# 25_SATA-SATA_PM0.net
KiCad netlist of a schematic drawn in Altium Designer
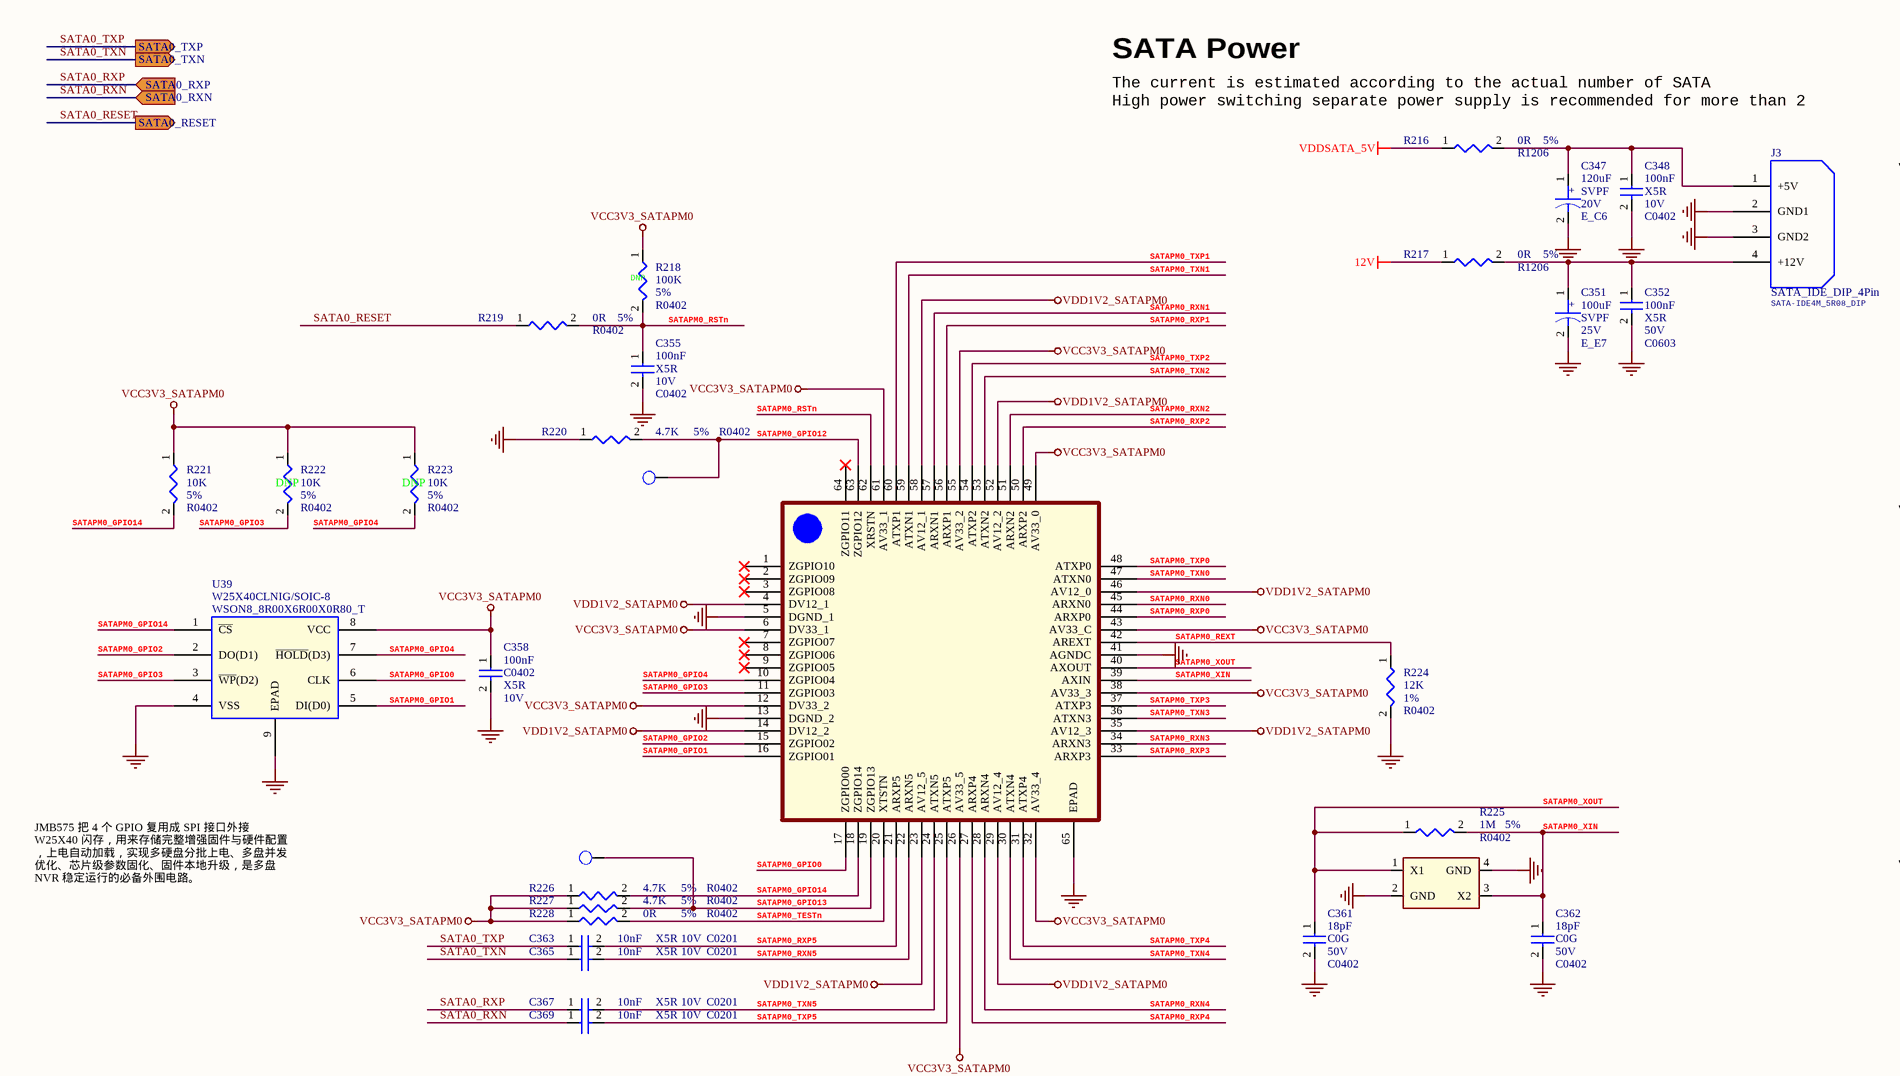
[diagram p0: 25_SATA-SATA PM0.SchDoc, top left]
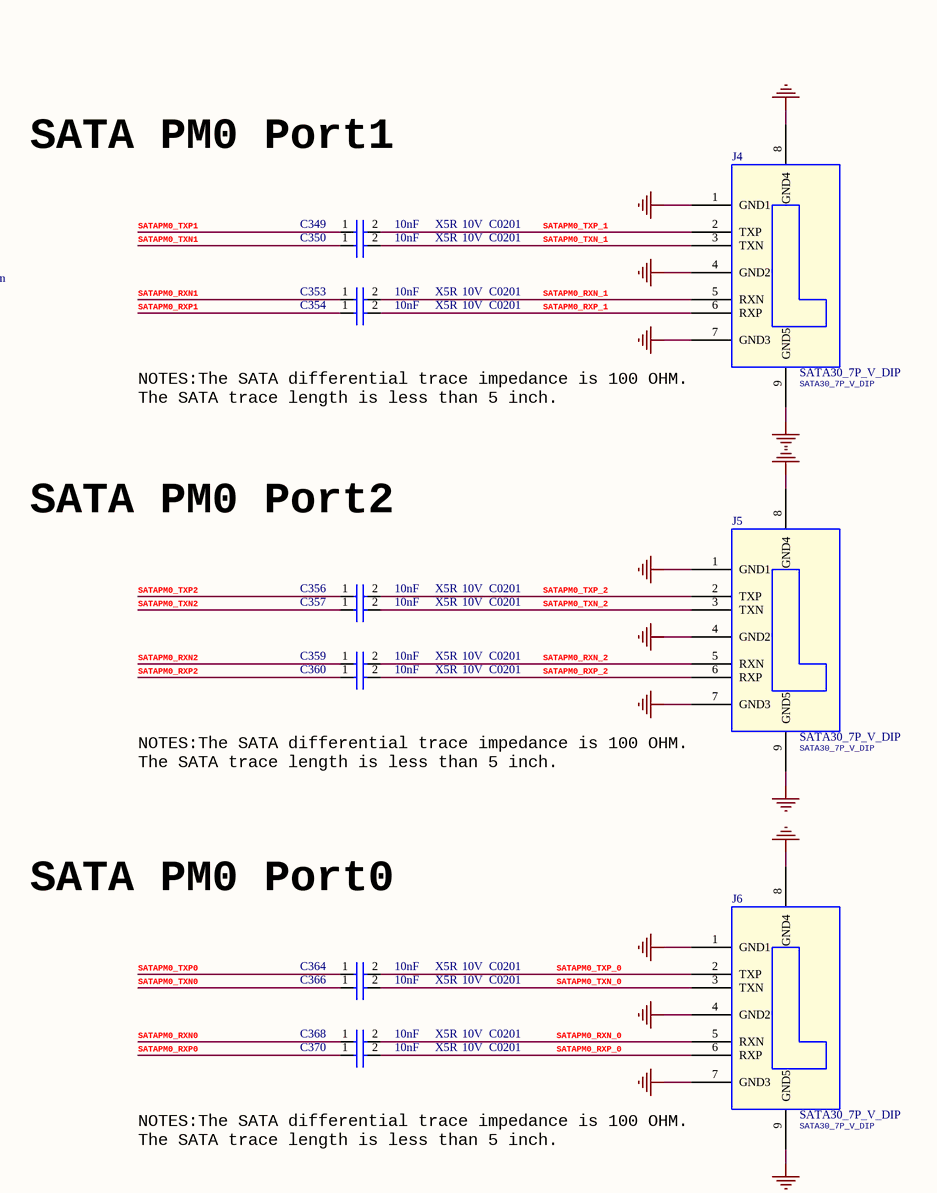
[diagram p1: 25_SATA-SATA PM0.SchDoc, top right]
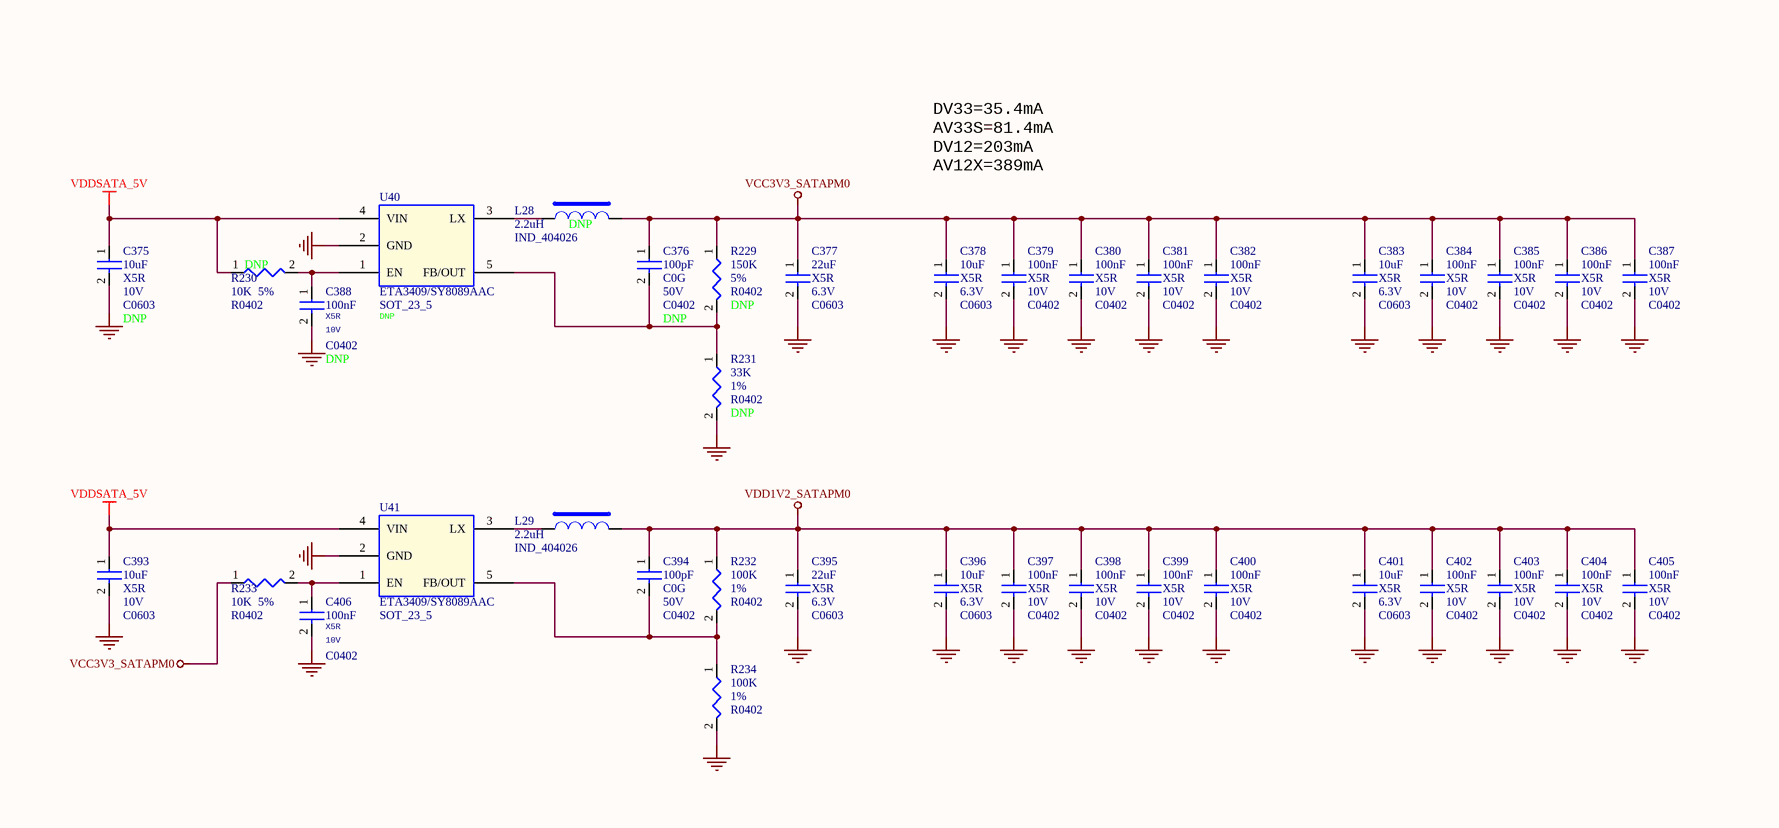
[diagram p2: 25_SATA-SATA PM0.SchDoc, bottom left]
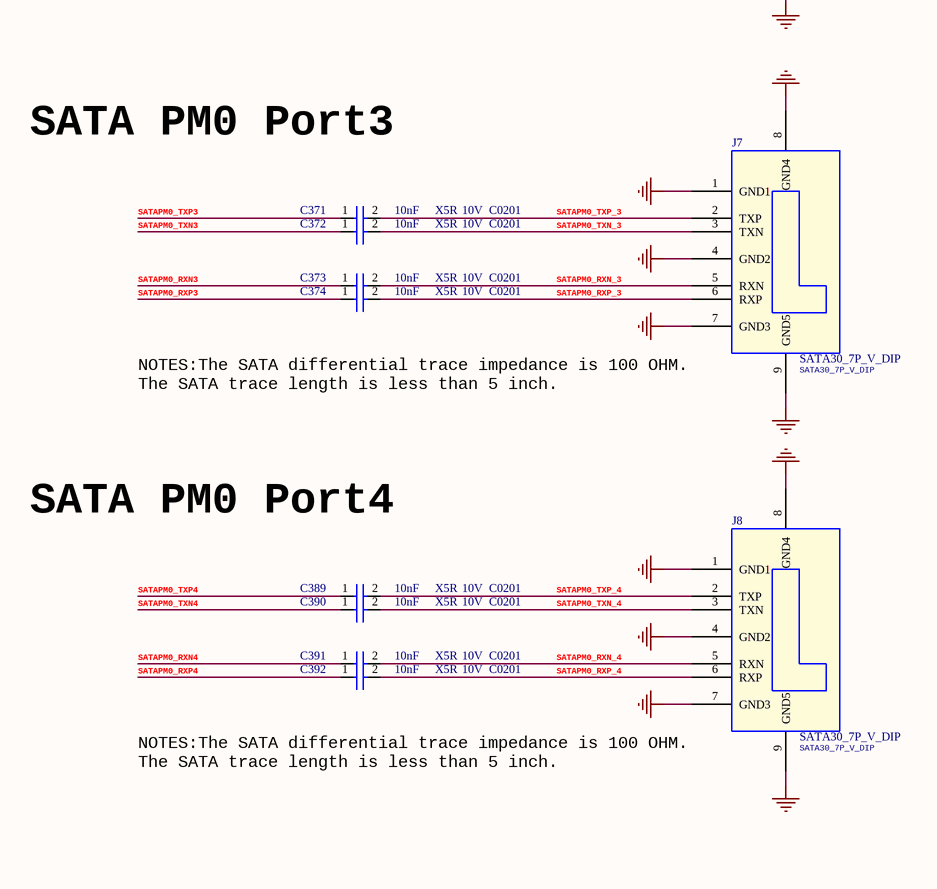
[diagram p3: 25_SATA-SATA PM0.SchDoc, bottom right]

(export (version "E")
  (design (tool "Eeschema 10.0.6"))
  (components
    (comp (ref "C347")
      (value "120uF")
      (footprint "E_C6")
      (description "120uF,20V,25mR,SVPF")
      (fields
        (field (name "VOLTAGE") "20V")
        (field (name "DIELECTRIC") "SVPF")
        (field (name "PCB FOOTPRINT") "E_C6")
        (field (name "MANUFACTURER") "Panasonic")
        (field (name "TOLERANCE") "20%")
        (field (name "CREATED BY") "JJJ")
      )
      (libsource (lib "*") (part "CAP"))
    )
    (comp (ref "C348")
      (value "100nF")
      (footprint "C0402")
      (description "cap,100.00nF,+/-10%,10V,X5R,C0402")
      (fields
        (field (name "VOLTAGE") "10V")
        (field (name "PCB FOOTPRINT") "C0402")
        (field (name "DIELECTRIC") "X5R")
        (field (name "TOLERANCE") "10%")
        (field (name "MANUFACTURER") "TDK")
        (field (name "CREATED BY") "JJJ")
      )
      (libsource (lib "*") (part "CAP NP"))
    )
    (comp (ref "C349")
      (value "10nF")
      (footprint "C0201")
      (description "cap,10.00nF,+/-10%,10V,X5R,C0201")
      (fields
        (field (name "VOLTAGE") "10V")
        (field (name "PCB FOOTPRINT") "C0201")
        (field (name "DIELECTRIC") "X5R")
        (field (name "MANUFACTURER") "TDK")
        (field (name "TOLERANCE") "10%")
        (field (name "CREATED BY") "JJJ")
      )
      (libsource (lib "*") (part "CAP NP"))
    )
    (comp (ref "C350")
      (value "10nF")
      (footprint "C0201")
      (description "cap,10.00nF,+/-10%,10V,X5R,C0201")
      (fields
        (field (name "VOLTAGE") "10V")
        (field (name "PCB FOOTPRINT") "C0201")
        (field (name "DIELECTRIC") "X5R")
        (field (name "MANUFACTURER") "TDK")
        (field (name "TOLERANCE") "10%")
        (field (name "CREATED BY") "JJJ")
      )
      (libsource (lib "*") (part "CAP NP"))
    )
    (comp (ref "C351")
      (value "100uF")
      (footprint "E_E7")
      (description "100uF,25V,24mR,SVPF")
      (fields
        (field (name "VOLTAGE") "25V")
        (field (name "DIELECTRIC") "SVPF")
        (field (name "PCB FOOTPRINT") "E_E7")
        (field (name "MANUFACTURER") "Panasonic")
        (field (name "TOLERANCE") "20%")
        (field (name "CREATED BY") "JJJ")
      )
      (libsource (lib "*") (part "CAP"))
    )
    (comp (ref "C352")
      (value "100nF")
      (footprint "C0603")
      (description "cap,100.00nF,+/-10%,50V,X5R,C0603")
      (fields
        (field (name "VOLTAGE") "50V")
        (field (name "PCB FOOTPRINT") "C0603")
        (field (name "DIELECTRIC") "X5R")
        (field (name "MANUFACTURER") "TDK")
        (field (name "TOLERANCE") "10%")
        (field (name "CREATED BY") "JJJ")
      )
      (libsource (lib "*") (part "CAP NP"))
    )
    (comp (ref "C353")
      (value "10nF")
      (footprint "C0201")
      (description "cap,10.00nF,+/-10%,10V,X5R,C0201")
      (fields
        (field (name "VOLTAGE") "10V")
        (field (name "PCB FOOTPRINT") "C0201")
        (field (name "DIELECTRIC") "X5R")
        (field (name "MANUFACTURER") "TDK")
        (field (name "TOLERANCE") "10%")
        (field (name "CREATED BY") "JJJ")
      )
      (libsource (lib "*") (part "CAP NP"))
    )
    (comp (ref "C354")
      (value "10nF")
      (footprint "C0201")
      (description "cap,10.00nF,+/-10%,10V,X5R,C0201")
      (fields
        (field (name "VOLTAGE") "10V")
        (field (name "PCB FOOTPRINT") "C0201")
        (field (name "DIELECTRIC") "X5R")
        (field (name "MANUFACTURER") "TDK")
        (field (name "TOLERANCE") "10%")
        (field (name "CREATED BY") "JJJ")
      )
      (libsource (lib "*") (part "CAP NP"))
    )
    (comp (ref "C355")
      (value "100nF")
      (footprint "C0402")
      (description "cap,100.00nF,+/-10%,10V,X5R,C0402")
      (fields
        (field (name "VOLTAGE") "10V")
        (field (name "PCB FOOTPRINT") "C0402")
        (field (name "DIELECTRIC") "X5R")
        (field (name "TOLERANCE") "10%")
        (field (name "MANUFACTURER") "TDK")
        (field (name "CREATED BY") "JJJ")
      )
      (libsource (lib "*") (part "CAP NP"))
    )
    (comp (ref "C356")
      (value "10nF")
      (footprint "C0201")
      (description "cap,10.00nF,+/-10%,10V,X5R,C0201")
      (fields
        (field (name "VOLTAGE") "10V")
        (field (name "PCB FOOTPRINT") "C0201")
        (field (name "DIELECTRIC") "X5R")
        (field (name "MANUFACTURER") "TDK")
        (field (name "TOLERANCE") "10%")
        (field (name "CREATED BY") "JJJ")
      )
      (libsource (lib "*") (part "CAP NP"))
    )
    (comp (ref "C357")
      (value "10nF")
      (footprint "C0201")
      (description "cap,10.00nF,+/-10%,10V,X5R,C0201")
      (fields
        (field (name "VOLTAGE") "10V")
        (field (name "PCB FOOTPRINT") "C0201")
        (field (name "DIELECTRIC") "X5R")
        (field (name "MANUFACTURER") "TDK")
        (field (name "TOLERANCE") "10%")
        (field (name "CREATED BY") "JJJ")
      )
      (libsource (lib "*") (part "CAP NP"))
    )
    (comp (ref "C358")
      (value "100nF")
      (footprint "C0402")
      (description "cap,100.00nF,+/-10%,10V,X5R,C0402")
      (fields
        (field (name "VOLTAGE") "10V")
        (field (name "PCB FOOTPRINT") "C0402")
        (field (name "DIELECTRIC") "X5R")
        (field (name "TOLERANCE") "10%")
        (field (name "MANUFACTURER") "TDK")
        (field (name "CREATED BY") "JJJ")
      )
      (libsource (lib "*") (part "CAP NP"))
    )
    (comp (ref "C359")
      (value "10nF")
      (footprint "C0201")
      (description "cap,10.00nF,+/-10%,10V,X5R,C0201")
      (fields
        (field (name "VOLTAGE") "10V")
        (field (name "PCB FOOTPRINT") "C0201")
        (field (name "DIELECTRIC") "X5R")
        (field (name "MANUFACTURER") "TDK")
        (field (name "TOLERANCE") "10%")
        (field (name "CREATED BY") "JJJ")
      )
      (libsource (lib "*") (part "CAP NP"))
    )
    (comp (ref "C360")
      (value "10nF")
      (footprint "C0201")
      (description "cap,10.00nF,+/-10%,10V,X5R,C0201")
      (fields
        (field (name "VOLTAGE") "10V")
        (field (name "PCB FOOTPRINT") "C0201")
        (field (name "DIELECTRIC") "X5R")
        (field (name "MANUFACTURER") "TDK")
        (field (name "TOLERANCE") "10%")
        (field (name "CREATED BY") "JJJ")
      )
      (libsource (lib "*") (part "CAP NP"))
    )
    (comp (ref "C361")
      (value "18pF")
      (footprint "C0402")
      (description "cap,18.00pF,+/-5%,50V,C0G,C0402")
      (fields
        (field (name "VOLTAGE") "50V")
        (field (name "PCB FOOTPRINT") "C0402")
        (field (name "DIELECTRIC") "C0G")
        (field (name "TOLERANCE") "5%")
        (field (name "MANUFACTURER") "TDK")
        (field (name "CREATED BY") "JJJ")
      )
      (libsource (lib "*") (part "CAP NP"))
    )
    (comp (ref "C362")
      (value "18pF")
      (footprint "C0402")
      (description "cap,18.00pF,+/-5%,50V,C0G,C0402")
      (fields
        (field (name "VOLTAGE") "50V")
        (field (name "PCB FOOTPRINT") "C0402")
        (field (name "DIELECTRIC") "C0G")
        (field (name "TOLERANCE") "5%")
        (field (name "MANUFACTURER") "TDK")
        (field (name "CREATED BY") "JJJ")
      )
      (libsource (lib "*") (part "CAP NP"))
    )
    (comp (ref "C363")
      (value "10nF")
      (footprint "C0201")
      (description "cap,10.00nF,+/-10%,10V,X5R,C0201")
      (fields
        (field (name "VOLTAGE") "10V")
        (field (name "PCB FOOTPRINT") "C0201")
        (field (name "DIELECTRIC") "X5R")
        (field (name "TOLERANCE") "10%")
        (field (name "MANUFACTURER") "TDK")
        (field (name "CREATED BY") "JJJ")
      )
      (libsource (lib "*") (part "CAP NP"))
    )
    (comp (ref "C364")
      (value "10nF")
      (footprint "C0201")
      (description "cap,10.00nF,+/-10%,10V,X5R,C0201")
      (fields
        (field (name "VOLTAGE") "10V")
        (field (name "PCB FOOTPRINT") "C0201")
        (field (name "DIELECTRIC") "X5R")
        (field (name "MANUFACTURER") "TDK")
        (field (name "TOLERANCE") "10%")
        (field (name "CREATED BY") "JJJ")
      )
      (libsource (lib "*") (part "CAP NP"))
    )
    (comp (ref "C365")
      (value "10nF")
      (footprint "C0201")
      (description "cap,10.00nF,+/-10%,10V,X5R,C0201")
      (fields
        (field (name "VOLTAGE") "10V")
        (field (name "PCB FOOTPRINT") "C0201")
        (field (name "DIELECTRIC") "X5R")
        (field (name "TOLERANCE") "10%")
        (field (name "MANUFACTURER") "TDK")
        (field (name "CREATED BY") "JJJ")
      )
      (libsource (lib "*") (part "CAP NP"))
    )
    (comp (ref "C366")
      (value "10nF")
      (footprint "C0201")
      (description "cap,10.00nF,+/-10%,10V,X5R,C0201")
      (fields
        (field (name "VOLTAGE") "10V")
        (field (name "PCB FOOTPRINT") "C0201")
        (field (name "DIELECTRIC") "X5R")
        (field (name "MANUFACTURER") "TDK")
        (field (name "TOLERANCE") "10%")
        (field (name "CREATED BY") "JJJ")
      )
      (libsource (lib "*") (part "CAP NP"))
    )
    (comp (ref "C367")
      (value "10nF")
      (footprint "C0201")
      (description "cap,10.00nF,+/-10%,10V,X5R,C0201")
      (fields
        (field (name "VOLTAGE") "10V")
        (field (name "PCB FOOTPRINT") "C0201")
        (field (name "DIELECTRIC") "X5R")
        (field (name "TOLERANCE") "10%")
        (field (name "MANUFACTURER") "TDK")
        (field (name "CREATED BY") "JJJ")
      )
      (libsource (lib "*") (part "CAP NP"))
    )
    (comp (ref "C368")
      (value "10nF")
      (footprint "C0201")
      (description "cap,10.00nF,+/-10%,10V,X5R,C0201")
      (fields
        (field (name "VOLTAGE") "10V")
        (field (name "PCB FOOTPRINT") "C0201")
        (field (name "DIELECTRIC") "X5R")
        (field (name "MANUFACTURER") "TDK")
        (field (name "TOLERANCE") "10%")
        (field (name "CREATED BY") "JJJ")
      )
      (libsource (lib "*") (part "CAP NP"))
    )
    (comp (ref "C369")
      (value "10nF")
      (footprint "C0201")
      (description "cap,10.00nF,+/-10%,10V,X5R,C0201")
      (fields
        (field (name "VOLTAGE") "10V")
        (field (name "PCB FOOTPRINT") "C0201")
        (field (name "DIELECTRIC") "X5R")
        (field (name "TOLERANCE") "10%")
        (field (name "MANUFACTURER") "TDK")
        (field (name "CREATED BY") "JJJ")
      )
      (libsource (lib "*") (part "CAP NP"))
    )
    (comp (ref "C370")
      (value "10nF")
      (footprint "C0201")
      (description "cap,10.00nF,+/-10%,10V,X5R,C0201")
      (fields
        (field (name "VOLTAGE") "10V")
        (field (name "PCB FOOTPRINT") "C0201")
        (field (name "DIELECTRIC") "X5R")
        (field (name "MANUFACTURER") "TDK")
        (field (name "TOLERANCE") "10%")
        (field (name "CREATED BY") "JJJ")
      )
      (libsource (lib "*") (part "CAP NP"))
    )
    (comp (ref "C371")
      (value "10nF")
      (footprint "C0201")
      (description "cap,10.00nF,+/-10%,10V,X5R,C0201")
      (fields
        (field (name "VOLTAGE") "10V")
        (field (name "PCB FOOTPRINT") "C0201")
        (field (name "DIELECTRIC") "X5R")
        (field (name "MANUFACTURER") "TDK")
        (field (name "TOLERANCE") "10%")
        (field (name "CREATED BY") "JJJ")
      )
      (libsource (lib "*") (part "CAP NP"))
    )
    (comp (ref "C372")
      (value "10nF")
      (footprint "C0201")
      (description "cap,10.00nF,+/-10%,10V,X5R,C0201")
      (fields
        (field (name "VOLTAGE") "10V")
        (field (name "PCB FOOTPRINT") "C0201")
        (field (name "DIELECTRIC") "X5R")
        (field (name "MANUFACTURER") "TDK")
        (field (name "TOLERANCE") "10%")
        (field (name "CREATED BY") "JJJ")
      )
      (libsource (lib "*") (part "CAP NP"))
    )
    (comp (ref "C373")
      (value "10nF")
      (footprint "C0201")
      (description "cap,10.00nF,+/-10%,10V,X5R,C0201")
      (fields
        (field (name "VOLTAGE") "10V")
        (field (name "PCB FOOTPRINT") "C0201")
        (field (name "DIELECTRIC") "X5R")
        (field (name "MANUFACTURER") "TDK")
        (field (name "TOLERANCE") "10%")
        (field (name "CREATED BY") "JJJ")
      )
      (libsource (lib "*") (part "CAP NP"))
    )
    (comp (ref "C374")
      (value "10nF")
      (footprint "C0201")
      (description "cap,10.00nF,+/-10%,10V,X5R,C0201")
      (fields
        (field (name "VOLTAGE") "10V")
        (field (name "PCB FOOTPRINT") "C0201")
        (field (name "DIELECTRIC") "X5R")
        (field (name "MANUFACTURER") "TDK")
        (field (name "TOLERANCE") "10%")
        (field (name "CREATED BY") "JJJ")
      )
      (libsource (lib "*") (part "CAP NP"))
    )
    (comp (ref "C375")
      (value "10uF")
      (footprint "C0603")
      (description "cap,10.00uF,+/-10%,10V,X5R,C0603")
      (fields
        (field (name "VOLTAGE") "10V")
        (field (name "PCB FOOTPRINT") "C0603")
        (field (name "DIELECTRIC") "X5R")
        (field (name "MANUFACTURER") "TDK")
        (field (name "TOLERANCE") "10%")
        (field (name "OPTION") "DNP")
        (field (name "CREATED BY") "JJJ")
      )
      (libsource (lib "*") (part "CAP NP"))
    )
    (comp (ref "C376")
      (value "100pF")
      (footprint "C0402")
      (description "cap,100.00pF,+/-10%,50V,C0G,C0402")
      (fields
        (field (name "VOLTAGE") "50V")
        (field (name "PCB FOOTPRINT") "C0402")
        (field (name "DIELECTRIC") "C0G")
        (field (name "TOLERANCE") "10%")
        (field (name "MANUFACTURER") "TDK")
        (field (name "OPTION") "DNP")
        (field (name "CREATED BY") "JJJ")
      )
      (libsource (lib "*") (part "CAP NP"))
    )
    (comp (ref "C377")
      (value "22uF")
      (footprint "C0603")
      (description "cap,22.00uF,+/-20%,6.3V,X5R,C0603")
      (fields
        (field (name "VOLTAGE") "6.3V")
        (field (name "PCB FOOTPRINT") "C0603")
        (field (name "DIELECTRIC") "X5R")
        (field (name "MANUFACTURER") "TDK")
        (field (name "TOLERANCE") "20%")
        (field (name "CREATED BY") "JJJ")
      )
      (libsource (lib "*") (part "CAP NP"))
    )
    (comp (ref "C378")
      (value "10uF")
      (footprint "C0603")
      (description "cap,10.00uF,+/-10%,6.3V,X5R,C0603")
      (fields
        (field (name "VOLTAGE") "6.3V")
        (field (name "PCB FOOTPRINT") "C0603")
        (field (name "DIELECTRIC") "X5R")
        (field (name "TOLERANCE") "10%")
        (field (name "MANUFACTURER") "TDK")
        (field (name "CREATED BY") "JJJ")
      )
      (libsource (lib "*") (part "CAP NP"))
    )
    (comp (ref "C379")
      (value "100nF")
      (footprint "C0402")
      (description "cap,100.00nF,+/-10%,10V,X5R,C0402")
      (fields
        (field (name "VOLTAGE") "10V")
        (field (name "PCB FOOTPRINT") "C0402")
        (field (name "DIELECTRIC") "X5R")
        (field (name "MANUFACTURER") "TDK")
        (field (name "TOLERANCE") "10%")
        (field (name "CREATED BY") "JJJ")
      )
      (libsource (lib "*") (part "CAP NP"))
    )
    (comp (ref "C380")
      (value "100nF")
      (footprint "C0402")
      (description "cap,100.00nF,+/-10%,10V,X5R,C0402")
      (fields
        (field (name "VOLTAGE") "10V")
        (field (name "PCB FOOTPRINT") "C0402")
        (field (name "DIELECTRIC") "X5R")
        (field (name "MANUFACTURER") "TDK")
        (field (name "TOLERANCE") "10%")
        (field (name "CREATED BY") "JJJ")
      )
      (libsource (lib "*") (part "CAP NP"))
    )
    (comp (ref "C381")
      (value "100nF")
      (footprint "C0402")
      (description "cap,100.00nF,+/-10%,10V,X5R,C0402")
      (fields
        (field (name "VOLTAGE") "10V")
        (field (name "PCB FOOTPRINT") "C0402")
        (field (name "DIELECTRIC") "X5R")
        (field (name "MANUFACTURER") "TDK")
        (field (name "TOLERANCE") "10%")
        (field (name "CREATED BY") "JJJ")
      )
      (libsource (lib "*") (part "CAP NP"))
    )
    (comp (ref "C382")
      (value "100nF")
      (footprint "C0402")
      (description "cap,100.00nF,+/-10%,10V,X5R,C0402")
      (fields
        (field (name "VOLTAGE") "10V")
        (field (name "PCB FOOTPRINT") "C0402")
        (field (name "DIELECTRIC") "X5R")
        (field (name "MANUFACTURER") "TDK")
        (field (name "TOLERANCE") "10%")
        (field (name "CREATED BY") "JJJ")
      )
      (libsource (lib "*") (part "CAP NP"))
    )
    (comp (ref "C383")
      (value "10uF")
      (footprint "C0603")
      (description "cap,10.00uF,+/-10%,6.3V,X5R,C0603")
      (fields
        (field (name "VOLTAGE") "6.3V")
        (field (name "PCB FOOTPRINT") "C0603")
        (field (name "DIELECTRIC") "X5R")
        (field (name "TOLERANCE") "10%")
        (field (name "MANUFACTURER") "TDK")
        (field (name "CREATED BY") "JJJ")
      )
      (libsource (lib "*") (part "CAP NP"))
    )
    (comp (ref "C384")
      (value "100nF")
      (footprint "C0402")
      (description "cap,100.00nF,+/-10%,10V,X5R,C0402")
      (fields
        (field (name "VOLTAGE") "10V")
        (field (name "PCB FOOTPRINT") "C0402")
        (field (name "DIELECTRIC") "X5R")
        (field (name "MANUFACTURER") "TDK")
        (field (name "TOLERANCE") "10%")
        (field (name "CREATED BY") "JJJ")
      )
      (libsource (lib "*") (part "CAP NP"))
    )
    (comp (ref "C385")
      (value "100nF")
      (footprint "C0402")
      (description "cap,100.00nF,+/-10%,10V,X5R,C0402")
      (fields
        (field (name "VOLTAGE") "10V")
        (field (name "PCB FOOTPRINT") "C0402")
        (field (name "DIELECTRIC") "X5R")
        (field (name "MANUFACTURER") "TDK")
        (field (name "TOLERANCE") "10%")
        (field (name "CREATED BY") "JJJ")
      )
      (libsource (lib "*") (part "CAP NP"))
    )
    (comp (ref "C386")
      (value "100nF")
      (footprint "C0402")
      (description "cap,100.00nF,+/-10%,10V,X5R,C0402")
      (fields
        (field (name "VOLTAGE") "10V")
        (field (name "PCB FOOTPRINT") "C0402")
        (field (name "DIELECTRIC") "X5R")
        (field (name "MANUFACTURER") "TDK")
        (field (name "TOLERANCE") "10%")
        (field (name "CREATED BY") "JJJ")
      )
      (libsource (lib "*") (part "CAP NP"))
    )
    (comp (ref "C387")
      (value "100nF")
      (footprint "C0402")
      (description "cap,100.00nF,+/-10%,10V,X5R,C0402")
      (fields
        (field (name "VOLTAGE") "10V")
        (field (name "PCB FOOTPRINT") "C0402")
        (field (name "DIELECTRIC") "X5R")
        (field (name "MANUFACTURER") "TDK")
        (field (name "TOLERANCE") "10%")
        (field (name "CREATED BY") "JJJ")
      )
      (libsource (lib "*") (part "CAP NP"))
    )
    (comp (ref "C388")
      (value "100nF")
      (footprint "C0402")
      (description "cap,100.00nF,+/-10%,10V,X5R,C0402")
      (fields
        (field (name "VOLTAGE") "10V")
        (field (name "PCB FOOTPRINT") "C0402")
        (field (name "DIELECTRIC") "X5R")
        (field (name "TOLERANCE") "10%")
        (field (name "MANUFACTURER") "TDK")
        (field (name "OPTION") "DNP")
        (field (name "CREATED BY") "JJJ")
      )
      (libsource (lib "*") (part "CAP NP"))
    )
    (comp (ref "C389")
      (value "10nF")
      (footprint "C0201")
      (description "cap,10.00nF,+/-10%,10V,X5R,C0201")
      (fields
        (field (name "VOLTAGE") "10V")
        (field (name "PCB FOOTPRINT") "C0201")
        (field (name "DIELECTRIC") "X5R")
        (field (name "MANUFACTURER") "TDK")
        (field (name "TOLERANCE") "10%")
        (field (name "CREATED BY") "JJJ")
      )
      (libsource (lib "*") (part "CAP NP"))
    )
    (comp (ref "C390")
      (value "10nF")
      (footprint "C0201")
      (description "cap,10.00nF,+/-10%,10V,X5R,C0201")
      (fields
        (field (name "VOLTAGE") "10V")
        (field (name "PCB FOOTPRINT") "C0201")
        (field (name "DIELECTRIC") "X5R")
        (field (name "MANUFACTURER") "TDK")
        (field (name "TOLERANCE") "10%")
        (field (name "CREATED BY") "JJJ")
      )
      (libsource (lib "*") (part "CAP NP"))
    )
    (comp (ref "C391")
      (value "10nF")
      (footprint "C0201")
      (description "cap,10.00nF,+/-10%,10V,X5R,C0201")
      (fields
        (field (name "VOLTAGE") "10V")
        (field (name "PCB FOOTPRINT") "C0201")
        (field (name "DIELECTRIC") "X5R")
        (field (name "MANUFACTURER") "TDK")
        (field (name "TOLERANCE") "10%")
        (field (name "CREATED BY") "JJJ")
      )
      (libsource (lib "*") (part "CAP NP"))
    )
    (comp (ref "C392")
      (value "10nF")
      (footprint "C0201")
      (description "cap,10.00nF,+/-10%,10V,X5R,C0201")
      (fields
        (field (name "VOLTAGE") "10V")
        (field (name "PCB FOOTPRINT") "C0201")
        (field (name "DIELECTRIC") "X5R")
        (field (name "MANUFACTURER") "TDK")
        (field (name "TOLERANCE") "10%")
        (field (name "CREATED BY") "JJJ")
      )
      (libsource (lib "*") (part "CAP NP"))
    )
    (comp (ref "C393")
      (value "10uF")
      (footprint "C0603")
      (description "cap,10.00uF,+/-10%,10V,X5R,C0603")
      (fields
        (field (name "VOLTAGE") "10V")
        (field (name "PCB FOOTPRINT") "C0603")
        (field (name "DIELECTRIC") "X5R")
        (field (name "TOLERANCE") "10%")
        (field (name "MANUFACTURER") "TDK")
        (field (name "CREATED BY") "JJJ")
      )
      (libsource (lib "*") (part "CAP NP"))
    )
    (comp (ref "C394")
      (value "100pF")
      (footprint "C0402")
      (description "cap,100.00pF,+/-10%,50V,C0G,C0402")
      (fields
        (field (name "VOLTAGE") "50V")
        (field (name "PCB FOOTPRINT") "C0402")
        (field (name "DIELECTRIC") "C0G")
        (field (name "MANUFACTURER") "TDK")
        (field (name "TOLERANCE") "10%")
        (field (name "CREATED BY") "JJJ")
      )
      (libsource (lib "*") (part "CAP NP"))
    )
    (comp (ref "C395")
      (value "22uF")
      (footprint "C0603")
      (description "cap,22.00uF,+/-20%,6.3V,X5R,C0603")
      (fields
        (field (name "VOLTAGE") "6.3V")
        (field (name "PCB FOOTPRINT") "C0603")
        (field (name "DIELECTRIC") "X5R")
        (field (name "TOLERANCE") "20%")
        (field (name "MANUFACTURER") "TDK")
        (field (name "CREATED BY") "JJJ")
      )
      (libsource (lib "*") (part "CAP NP"))
    )
    (comp (ref "C396")
      (value "10uF")
      (footprint "C0603")
      (description "cap,10.00uF,+/-10%,6.3V,X5R,C0603")
      (fields
        (field (name "VOLTAGE") "6.3V")
        (field (name "PCB FOOTPRINT") "C0603")
        (field (name "DIELECTRIC") "X5R")
        (field (name "TOLERANCE") "10%")
        (field (name "MANUFACTURER") "TDK")
        (field (name "CREATED BY") "JJJ")
      )
      (libsource (lib "*") (part "CAP NP"))
    )
    (comp (ref "C397")
      (value "100nF")
      (footprint "C0402")
      (description "cap,100.00nF,+/-10%,10V,X5R,C0402")
      (fields
        (field (name "VOLTAGE") "10V")
        (field (name "PCB FOOTPRINT") "C0402")
        (field (name "DIELECTRIC") "X5R")
        (field (name "MANUFACTURER") "TDK")
        (field (name "TOLERANCE") "10%")
        (field (name "CREATED BY") "JJJ")
      )
      (libsource (lib "*") (part "CAP NP"))
    )
    (comp (ref "C398")
      (value "100nF")
      (footprint "C0402")
      (description "cap,100.00nF,+/-10%,10V,X5R,C0402")
      (fields
        (field (name "VOLTAGE") "10V")
        (field (name "PCB FOOTPRINT") "C0402")
        (field (name "DIELECTRIC") "X5R")
        (field (name "MANUFACTURER") "TDK")
        (field (name "TOLERANCE") "10%")
        (field (name "CREATED BY") "JJJ")
      )
      (libsource (lib "*") (part "CAP NP"))
    )
    (comp (ref "C399")
      (value "100nF")
      (footprint "C0402")
      (description "cap,100.00nF,+/-10%,10V,X5R,C0402")
      (fields
        (field (name "VOLTAGE") "10V")
        (field (name "PCB FOOTPRINT") "C0402")
        (field (name "DIELECTRIC") "X5R")
        (field (name "MANUFACTURER") "TDK")
        (field (name "TOLERANCE") "10%")
        (field (name "CREATED BY") "JJJ")
      )
      (libsource (lib "*") (part "CAP NP"))
    )
    (comp (ref "C400")
      (value "100nF")
      (footprint "C0402")
      (description "cap,100.00nF,+/-10%,10V,X5R,C0402")
      (fields
        (field (name "VOLTAGE") "10V")
        (field (name "PCB FOOTPRINT") "C0402")
        (field (name "DIELECTRIC") "X5R")
        (field (name "MANUFACTURER") "TDK")
        (field (name "TOLERANCE") "10%")
        (field (name "CREATED BY") "JJJ")
      )
      (libsource (lib "*") (part "CAP NP"))
    )
    (comp (ref "C401")
      (value "10uF")
      (footprint "C0603")
      (description "cap,10.00uF,+/-10%,6.3V,X5R,C0603")
      (fields
        (field (name "VOLTAGE") "6.3V")
        (field (name "PCB FOOTPRINT") "C0603")
        (field (name "DIELECTRIC") "X5R")
        (field (name "TOLERANCE") "10%")
        (field (name "MANUFACTURER") "TDK")
        (field (name "CREATED BY") "JJJ")
      )
      (libsource (lib "*") (part "CAP NP"))
    )
    (comp (ref "C402")
      (value "100nF")
      (footprint "C0402")
      (description "cap,100.00nF,+/-10%,10V,X5R,C0402")
      (fields
        (field (name "VOLTAGE") "10V")
        (field (name "PCB FOOTPRINT") "C0402")
        (field (name "DIELECTRIC") "X5R")
        (field (name "MANUFACTURER") "TDK")
        (field (name "TOLERANCE") "10%")
        (field (name "CREATED BY") "JJJ")
      )
      (libsource (lib "*") (part "CAP NP"))
    )
    (comp (ref "C403")
      (value "100nF")
      (footprint "C0402")
      (description "cap,100.00nF,+/-10%,10V,X5R,C0402")
      (fields
        (field (name "VOLTAGE") "10V")
        (field (name "PCB FOOTPRINT") "C0402")
        (field (name "DIELECTRIC") "X5R")
        (field (name "MANUFACTURER") "TDK")
        (field (name "TOLERANCE") "10%")
        (field (name "CREATED BY") "JJJ")
      )
      (libsource (lib "*") (part "CAP NP"))
    )
    (comp (ref "C404")
      (value "100nF")
      (footprint "C0402")
      (description "cap,100.00nF,+/-10%,10V,X5R,C0402")
      (fields
        (field (name "VOLTAGE") "10V")
        (field (name "PCB FOOTPRINT") "C0402")
        (field (name "DIELECTRIC") "X5R")
        (field (name "MANUFACTURER") "TDK")
        (field (name "TOLERANCE") "10%")
        (field (name "CREATED BY") "JJJ")
      )
      (libsource (lib "*") (part "CAP NP"))
    )
    (comp (ref "C405")
      (value "100nF")
      (footprint "C0402")
      (description "cap,100.00nF,+/-10%,10V,X5R,C0402")
      (fields
        (field (name "VOLTAGE") "10V")
        (field (name "PCB FOOTPRINT") "C0402")
        (field (name "DIELECTRIC") "X5R")
        (field (name "MANUFACTURER") "TDK")
        (field (name "TOLERANCE") "10%")
        (field (name "CREATED BY") "JJJ")
      )
      (libsource (lib "*") (part "CAP NP"))
    )
    (comp (ref "C406")
      (value "100nF")
      (footprint "C0402")
      (description "cap,100.00nF,+/-10%,10V,X5R,C0402")
      (fields
        (field (name "VOLTAGE") "10V")
        (field (name "PCB FOOTPRINT") "C0402")
        (field (name "DIELECTRIC") "X5R")
        (field (name "MANUFACTURER") "TDK")
        (field (name "TOLERANCE") "10%")
        (field (name "CREATED BY") "JJJ")
      )
      (libsource (lib "*") (part "CAP NP"))
    )
    (comp (ref "J3")
      (value "SATA_IDE_DIP_4Pin")
      (footprint "SATA-IDE4M_5R08_DIP")
      (fields (field (name "PCB FOOTPRINT") "SATA-IDE4M_5R08_DIP"))
      (libsource (lib "*") (part "SATA_IDE_DIP_0"))
    )
    (comp (ref "J4")
      (value "SATA30_7P_V_DIP")
      (footprint "SATA30_7P_V_DIP")
      (fields (field (name "PCB FOOTPRINT") "SATA30_7P_V_DIP"))
      (libsource (lib "*") (part "SATA_DIP_0"))
    )
    (comp (ref "J5")
      (value "SATA30_7P_V_DIP")
      (footprint "SATA30_7P_V_DIP")
      (fields (field (name "PCB FOOTPRINT") "SATA30_7P_V_DIP"))
      (libsource (lib "*") (part "SATA_DIP_0"))
    )
    (comp (ref "J6")
      (value "SATA30_7P_V_DIP")
      (footprint "SATA30_7P_V_DIP")
      (fields (field (name "PCB FOOTPRINT") "SATA30_7P_V_DIP"))
      (libsource (lib "*") (part "SATA_DIP_0"))
    )
    (comp (ref "J7")
      (value "SATA30_7P_V_DIP")
      (footprint "SATA30_7P_V_DIP")
      (fields (field (name "PCB FOOTPRINT") "SATA30_7P_V_DIP"))
      (libsource (lib "*") (part "SATA_DIP_0"))
    )
    (comp (ref "J8")
      (value "SATA30_7P_V_DIP")
      (footprint "SATA30_7P_V_DIP")
      (fields (field (name "PCB FOOTPRINT") "SATA30_7P_V_DIP"))
      (libsource (lib "*") (part "SATA_DIP_0"))
    )
    (comp (ref "L28")
      (value "2.2uH")
      (footprint "IND_404026")
      (description "Power Inductor,2.2uH,0.2,IND_404026")
      (fields
        (field (name "PCB FOOTPRINT") "IND_404026")
        (field (name "TOLERANCE") "20%")
        (field (name "MANUFACTURER") "sunlord")
        (field (name "OPTION") "DNP")
        (field (name "CREATED BY") "YTL")
      )
      (libsource (lib "*") (part "INDUCTORS OF FERRITE_Dup1"))
    )
    (comp (ref "L29")
      (value "2.2uH")
      (footprint "IND_404026")
      (description "Power Inductor,2.2uH,0.2,IND_404026")
      (fields
        (field (name "PCB FOOTPRINT") "IND_404026")
        (field (name "MANUFACTURER") "sunlord")
        (field (name "TOLERANCE") "20%")
        (field (name "CREATED BY") "YTL")
      )
      (libsource (lib "*") (part "INDUCTORS OF FERRITE_Dup1"))
    )
    (comp (ref "R216")
      (value "0R")
      (footprint "R0402")
      (description "通用厚膜电阻,0R,+/-5%,R1206,1/4W.")
      (fields
        (field (name "PCB FOOTPRINT") "R1206")
        (field (name "TOLERANCE") "5%")
        (field (name "MANUFACTURER") "YAGEO")
        (field (name "CREATED BY") "YTL")
      )
      (libsource (lib "*") (part "RESISTOR_Dup1"))
    )
    (comp (ref "R217")
      (value "0R")
      (footprint "R0402")
      (description "通用厚膜电阻,0R,+/-5%,R1206,1/4W.")
      (fields
        (field (name "PCB FOOTPRINT") "R1206")
        (field (name "TOLERANCE") "5%")
        (field (name "MANUFACTURER") "YAGEO")
        (field (name "CREATED BY") "YTL")
      )
      (libsource (lib "*") (part "RESISTOR_Dup1"))
    )
    (comp (ref "R218")
      (value "100K")
      (footprint "R0402")
      (description "通用厚膜电阻,100K,+/-5%,R0402,1/16W.")
      (fields
        (field (name "PCB FOOTPRINT") "R0402")
        (field (name "TOLERANCE") "5%")
        (field (name "MANUFACTURER") "YAGEO")
        (field (name "OPTION") "DNP")
        (field (name "CREATED BY") "YTL")
      )
      (libsource (lib "*") (part "RESISTOR_Dup1"))
    )
    (comp (ref "R219")
      (value "0R")
      (footprint "R0402")
      (description "通用厚膜电阻,0R,+/-5%,R0402,1/16W.")
      (fields
        (field (name "PCB FOOTPRINT") "R0402")
        (field (name "TOLERANCE") "5%")
        (field (name "MANUFACTURER") "YAGEO")
        (field (name "CREATED BY") "YTL")
      )
      (libsource (lib "*") (part "RESISTOR_Dup1"))
    )
    (comp (ref "R220")
      (value "4.7K")
      (footprint "R0402")
      (description "通用厚膜电阻,4K7,+/-5%,R0402,1/16W.")
      (fields
        (field (name "PCB FOOTPRINT") "R0402")
        (field (name "TOLERANCE") "5%")
        (field (name "MANUFACTURER") "YAGEO")
        (field (name "CREATED BY") "YTL")
      )
      (libsource (lib "*") (part "RESISTOR_Dup1"))
    )
    (comp (ref "R221")
      (value "10K")
      (footprint "R0402")
      (description "通用厚膜电阻,10K,+/-5%,R0402,1/16W.")
      (fields
        (field (name "PCB FOOTPRINT") "R0402")
        (field (name "TOLERANCE") "5%")
        (field (name "MANUFACTURER") "YAGEO")
        (field (name "CREATED BY") "YTL")
      )
      (libsource (lib "*") (part "RESISTOR_Dup1"))
    )
    (comp (ref "R222")
      (value "10K")
      (footprint "R0402")
      (description "通用厚膜电阻,10K,+/-5%,R0402,1/16W.")
      (fields
        (field (name "PCB FOOTPRINT") "R0402")
        (field (name "TOLERANCE") "5%")
        (field (name "OPTION") "DNP")
        (field (name "MANUFACTURER") "YAGEO")
        (field (name "CREATED BY") "YTL")
      )
      (libsource (lib "*") (part "RESISTOR_Dup1"))
    )
    (comp (ref "R223")
      (value "10K")
      (footprint "R0402")
      (description "通用厚膜电阻,10K,+/-5%,R0402,1/16W.")
      (fields
        (field (name "PCB FOOTPRINT") "R0402")
        (field (name "TOLERANCE") "5%")
        (field (name "MANUFACTURER") "YAGEO")
        (field (name "OPTION") "DNP")
        (field (name "CREATED BY") "YTL")
      )
      (libsource (lib "*") (part "RESISTOR_Dup1"))
    )
    (comp (ref "R224")
      (value "12K")
      (footprint "R0402")
      (description "通用厚膜电阻,12K,+/-1%,R0402,1/16W.")
      (fields
        (field (name "PCB FOOTPRINT") "R0402")
        (field (name "TOLERANCE") "1%")
        (field (name "MANUFACTURER") "YAGEO")
        (field (name "CREATED BY") "YTL")
      )
      (libsource (lib "*") (part "RESISTOR_Dup1"))
    )
    (comp (ref "R225")
      (value "1M")
      (footprint "R0402")
      (description "通用厚膜电阻,1M,+/-5%,R0402,1/16W.")
      (fields
        (field (name "PCB FOOTPRINT") "R0402")
        (field (name "TOLERANCE") "5%")
        (field (name "MANUFACTURER") "YAGEO")
        (field (name "CREATED BY") "YTL")
      )
      (libsource (lib "*") (part "RESISTOR_Dup1"))
    )
    (comp (ref "R226")
      (value "4.7K")
      (footprint "R0402")
      (description "通用厚膜电阻,4K7,+/-5%,R0402,1/16W.")
      (fields
        (field (name "PCB FOOTPRINT") "R0402")
        (field (name "TOLERANCE") "5%")
        (field (name "MANUFACTURER") "YAGEO")
        (field (name "CREATED BY") "YTL")
      )
      (libsource (lib "*") (part "RESISTOR_Dup1"))
    )
    (comp (ref "R227")
      (value "4.7K")
      (footprint "R0402")
      (description "通用厚膜电阻,4K7,+/-5%,R0402,1/16W.")
      (fields
        (field (name "PCB FOOTPRINT") "R0402")
        (field (name "TOLERANCE") "5%")
        (field (name "MANUFACTURER") "YAGEO")
        (field (name "CREATED BY") "YTL")
      )
      (libsource (lib "*") (part "RESISTOR_Dup1"))
    )
    (comp (ref "R228")
      (value "0R")
      (footprint "R0402")
      (description "通用厚膜电阻,0R,+/-5%,R0402,1/16W.")
      (fields
        (field (name "PCB FOOTPRINT") "R0402")
        (field (name "TOLERANCE") "5%")
        (field (name "MANUFACTURER") "YAGEO")
        (field (name "CREATED BY") "YTL")
      )
      (libsource (lib "*") (part "RESISTOR_Dup1"))
    )
    (comp (ref "R229")
      (value "150K")
      (footprint "R0402")
      (description "通用厚膜电阻,150K,+/-5%,R0402,1/16W.")
      (fields
        (field (name "PCB FOOTPRINT") "R0402")
        (field (name "TOLERANCE") "5%")
        (field (name "OPTION") "DNP")
        (field (name "MANUFACTURER") "YAGEO")
        (field (name "CREATED BY") "YTL")
      )
      (libsource (lib "*") (part "RESISTOR_Dup1"))
    )
    (comp (ref "R230")
      (value "10K")
      (footprint "R0402")
      (description "通用厚膜电阻,10K,+/-5%,R0402,1/16W.")
      (fields
        (field (name "PCB FOOTPRINT") "R0402")
        (field (name "TOLERANCE") "5%")
        (field (name "MANUFACTURER") "YAGEO")
        (field (name "OPTION") "DNP")
        (field (name "CREATED BY") "YTL")
      )
      (libsource (lib "*") (part "RESISTOR_Dup1"))
    )
    (comp (ref "R231")
      (value "33K")
      (footprint "R0402")
      (description "通用厚膜电阻,33K,+/-1%,R0402,1/16W.")
      (fields
        (field (name "PCB FOOTPRINT") "R0402")
        (field (name "TOLERANCE") "1%")
        (field (name "MANUFACTURER") "YAGEO")
        (field (name "OPTION") "DNP")
        (field (name "CREATED BY") "YTL")
      )
      (libsource (lib "*") (part "RESISTOR_Dup1"))
    )
    (comp (ref "R232")
      (value "100K")
      (footprint "R0402")
      (description "通用厚膜电阻,100K,+/-1%,R0402,1/16W.")
      (fields
        (field (name "PCB FOOTPRINT") "R0402")
        (field (name "TOLERANCE") "1%")
        (field (name "MANUFACTURER") "YAGEO")
        (field (name "CREATED BY") "YTL")
      )
      (libsource (lib "*") (part "RESISTOR_Dup1"))
    )
    (comp (ref "R233")
      (value "10K")
      (footprint "R0402")
      (description "通用厚膜电阻,10K,+/-5%,R0402,1/16W.")
      (fields
        (field (name "PCB FOOTPRINT") "R0402")
        (field (name "TOLERANCE") "5%")
        (field (name "MANUFACTURER") "YAGEO")
        (field (name "CREATED BY") "YTL")
      )
      (libsource (lib "*") (part "RESISTOR_Dup1"))
    )
    (comp (ref "R234")
      (value "100K")
      (footprint "R0402")
      (description "通用厚膜电阻,100K,+/-1%,R0402,1/16W.")
      (fields
        (field (name "PCB FOOTPRINT") "R0402")
        (field (name "TOLERANCE") "1%")
        (field (name "MANUFACTURER") "YAGEO")
        (field (name "CREATED BY") "YTL")
      )
      (libsource (lib "*") (part "RESISTOR_Dup1"))
    )
    (comp (ref "TP3") (value "TP") (footprint "TP_0R70") (libsource (lib "RK3568核心板") (part "TP")))
    (comp (ref "TP4") (value "TP") (footprint "TP_0R70") (libsource (lib "RK3568核心板") (part "TP")))
    (comp (ref "U38")
      (value "JMB575")
      (footprint "QFN64_9R00X9R00X0R90_T")
      (libsource (lib "RK3568核心板") (part "JMB575"))
    )
    (comp (ref "U39")
      (value "W25X40CLNIG/SOIC-8")
      (footprint "WSON8_8R00X6R00X0R80_T")
      (description "256M-bit Serial Flash;32M-byte;3.3V Uniform Sector;Dual and Quad Serial Flash;")
      (fields
        (field (name "PCB FOOTPRINT") "WSON8_8R00X6R00X0R80_T")
        (field (name "MANUFACTURER") "GigaDevice")
        (field (name "CREATED BY") "JJJ")
      )
      (libsource (lib "*") (part "SPI_FLASH_8PIN_T_0"))
    )
    (comp (ref "U40")
      (value "ETA3409/SY8089AAC")
      (footprint "SOT_23_5")
      (description "High Efficiency 5.5V, 2A continuous, 3A peak, 1MHz Synchronous Step Down Regulator")
      (fields
        (field (name "PCB FOOTPRINT") "SOT_23_5")
        (field (name "MANUFACTURER") "Silergy（矽力杰）")
        (field (name "OPTION") "DNP")
        (field (name "CREATED BY") "JJJ")
      )
      (libsource (lib "*") (part "DCDC_SY8088"))
    )
    (comp (ref "U41")
      (value "ETA3409/SY8089AAC")
      (footprint "SOT_23_5")
      (description "High Efficiency 5.5V, 2A continuous, 3A peak, 1MHz Synchronous Step Down Regulator")
      (fields
        (field (name "PCB FOOTPRINT") "SOT_23_5")
        (field (name "MANUFACTURER") "Silergy（矽力杰）")
        (field (name "CREATED BY") "JJJ")
      )
      (libsource (lib "*") (part "DCDC_SY8088"))
    )
    (comp (ref "Y4")
      (value "CRYSTAL_4P")
      (footprint "CRY4_3R20X2R50X0R80")
      (libsource (lib "RK3568核心板") (part "CRYSTAL_4P"))
    )
  )
  (nets
    (net (code "1") (name "/SATA0_RESET") (class "Default")
      (node (ref "R219") (pin "1") (pinfunction "1_1") (pintype "passive"))
    )
    (net (code "2") (name "/SATA0_RXN") (class "Default")
      (node (ref "C369") (pin "1") (pinfunction "1_1") (pintype "passive"))
    )
    (net (code "3") (name "/SATA0_RXP") (class "Default")
      (node (ref "C367") (pin "1") (pinfunction "1_1") (pintype "passive"))
    )
    (net (code "4") (name "/SATA0_TXN") (class "Default")
      (node (ref "C365") (pin "1") (pinfunction "1_1") (pintype "passive"))
    )
    (net (code "5") (name "/SATA0_TXP") (class "Default")
      (node (ref "C363") (pin "1") (pinfunction "1_1") (pintype "passive"))
    )
    (net (code "6") (name "/SATAPM0_GPIO0") (class "Default")
      (node (ref "U38") (pin "17") (pinfunction "ZGPIO00_17") (pintype "passive"))
      (node (ref "U39") (pin "6") (pinfunction "CLK_6") (pintype "passive"))
    )
    (net (code "7") (name "/SATAPM0_GPIO1") (class "Default")
      (node (ref "U38") (pin "16") (pinfunction "ZGPIO01_16") (pintype "passive"))
      (node (ref "U39") (pin "5") (pinfunction "DI(D0)_5") (pintype "passive"))
    )
    (net (code "8") (name "/SATAPM0_GPIO2") (class "Default")
      (node (ref "U38") (pin "15") (pinfunction "ZGPIO02_15") (pintype "passive"))
      (node (ref "U39") (pin "2") (pinfunction "DO(D1)_2") (pintype "passive"))
    )
    (net (code "9") (name "/SATAPM0_GPIO3") (class "Default")
      (node (ref "R222") (pin "2") (pinfunction "2_2") (pintype "passive"))
      (node (ref "U38") (pin "11") (pinfunction "ZGPIO03_11") (pintype "passive"))
      (node (ref "U39") (pin "3") (pinfunction "~{WP}(D2)_3") (pintype "passive"))
    )
    (net (code "10") (name "/SATAPM0_GPIO4") (class "Default")
      (node (ref "R223") (pin "2") (pinfunction "2_2") (pintype "passive"))
      (node (ref "U38") (pin "10") (pinfunction "ZGPIO04_10") (pintype "passive"))
      (node (ref "U39") (pin "7") (pinfunction "~{HOLD}(D3)_7") (pintype "passive"))
    )
    (net (code "11") (name "/SATAPM0_GPIO12") (class "Default")
      (node (ref "R220") (pin "2") (pinfunction "2_2") (pintype "passive"))
      (node (ref "TP3") (pin "1") (pinfunction "1_1") (pintype "passive"))
      (node (ref "U38") (pin "63") (pinfunction "ZGPIO12_63") (pintype "passive"))
    )
    (net (code "12") (name "/SATAPM0_GPIO13") (class "Default")
      (node (ref "R227") (pin "2") (pinfunction "2_2") (pintype "passive"))
      (node (ref "TP4") (pin "1") (pinfunction "1_1") (pintype "passive"))
      (node (ref "U38") (pin "19") (pinfunction "ZGPIO13_19") (pintype "passive"))
    )
    (net (code "13") (name "/SATAPM0_GPIO14") (class "Default")
      (node (ref "R221") (pin "2") (pinfunction "2_2") (pintype "passive"))
      (node (ref "R226") (pin "2") (pinfunction "2_2") (pintype "passive"))
      (node (ref "U38") (pin "18") (pinfunction "ZGPIO14_18") (pintype "passive"))
      (node (ref "U39") (pin "1") (pinfunction "~{CS}_1") (pintype "passive"))
    )
    (net (code "14") (name "/SATAPM0_REXT") (class "Default")
      (node (ref "R224") (pin "1") (pinfunction "1_1") (pintype "passive"))
      (node (ref "U38") (pin "42") (pinfunction "AREXT_42") (pintype "passive"))
    )
    (net (code "15") (name "/SATAPM0_RSTn") (class "Default")
      (node (ref "C355") (pin "1") (pinfunction "1_1") (pintype "passive"))
      (node (ref "R218") (pin "2") (pinfunction "2_2") (pintype "passive"))
      (node (ref "R219") (pin "2") (pinfunction "2_2") (pintype "passive"))
      (node (ref "U38") (pin "62") (pinfunction "XRSTN_62") (pintype "passive"))
    )
    (net (code "16") (name "/SATAPM0_RXN0") (class "Default")
      (node (ref "C368") (pin "1") (pinfunction "1_1") (pintype "passive"))
      (node (ref "U38") (pin "45") (pinfunction "ARXN0_45") (pintype "passive"))
    )
    (net (code "17") (name "/SATAPM0_RXN1") (class "Default")
      (node (ref "C353") (pin "1") (pinfunction "1_1") (pintype "passive"))
      (node (ref "U38") (pin "57") (pinfunction "ARXN1_57") (pintype "passive"))
    )
    (net (code "18") (name "/SATAPM0_RXN2") (class "Default")
      (node (ref "C359") (pin "1") (pinfunction "1_1") (pintype "passive"))
      (node (ref "U38") (pin "51") (pinfunction "ARXN2_51") (pintype "passive"))
    )
    (net (code "19") (name "/SATAPM0_RXN3") (class "Default")
      (node (ref "C373") (pin "1") (pinfunction "1_1") (pintype "passive"))
      (node (ref "U38") (pin "34") (pinfunction "ARXN3_34") (pintype "passive"))
    )
    (net (code "20") (name "/SATAPM0_RXN4") (class "Default")
      (node (ref "C391") (pin "1") (pinfunction "1_1") (pintype "passive"))
      (node (ref "U38") (pin "28") (pinfunction "ARXN4_28") (pintype "passive"))
    )
    (net (code "21") (name "/SATAPM0_RXN5") (class "Default")
      (node (ref "C365") (pin "2") (pinfunction "2_2") (pintype "passive"))
      (node (ref "U38") (pin "22") (pinfunction "ARXN5_22") (pintype "passive"))
    )
    (net (code "22") (name "/SATAPM0_RXN_0") (class "Default")
      (node (ref "C368") (pin "2") (pinfunction "2_2") (pintype "passive"))
      (node (ref "J6") (pin "5") (pinfunction "RXN_5") (pintype "passive"))
    )
    (net (code "23") (name "/SATAPM0_RXN_1") (class "Default")
      (node (ref "C353") (pin "2") (pinfunction "2_2") (pintype "passive"))
      (node (ref "J4") (pin "5") (pinfunction "RXN_5") (pintype "passive"))
    )
    (net (code "24") (name "/SATAPM0_RXN_2") (class "Default")
      (node (ref "C359") (pin "2") (pinfunction "2_2") (pintype "passive"))
      (node (ref "J5") (pin "5") (pinfunction "RXN_5") (pintype "passive"))
    )
    (net (code "25") (name "/SATAPM0_RXN_3") (class "Default")
      (node (ref "C373") (pin "2") (pinfunction "2_2") (pintype "passive"))
      (node (ref "J7") (pin "5") (pinfunction "RXN_5") (pintype "passive"))
    )
    (net (code "26") (name "/SATAPM0_RXN_4") (class "Default")
      (node (ref "C391") (pin "2") (pinfunction "2_2") (pintype "passive"))
      (node (ref "J8") (pin "5") (pinfunction "RXN_5") (pintype "passive"))
    )
    (net (code "27") (name "/SATAPM0_RXP0") (class "Default")
      (node (ref "C370") (pin "1") (pinfunction "1_1") (pintype "passive"))
      (node (ref "U38") (pin "44") (pinfunction "ARXP0_44") (pintype "passive"))
    )
    (net (code "28") (name "/SATAPM0_RXP1") (class "Default")
      (node (ref "C354") (pin "1") (pinfunction "1_1") (pintype "passive"))
      (node (ref "U38") (pin "56") (pinfunction "ARXP1_56") (pintype "passive"))
    )
    (net (code "29") (name "/SATAPM0_RXP2") (class "Default")
      (node (ref "C360") (pin "1") (pinfunction "1_1") (pintype "passive"))
      (node (ref "U38") (pin "50") (pinfunction "ARXP2_50") (pintype "passive"))
    )
    (net (code "30") (name "/SATAPM0_RXP3") (class "Default")
      (node (ref "C374") (pin "1") (pinfunction "1_1") (pintype "passive"))
      (node (ref "U38") (pin "33") (pinfunction "ARXP3_33") (pintype "passive"))
    )
    (net (code "31") (name "/SATAPM0_RXP4") (class "Default")
      (node (ref "C392") (pin "1") (pinfunction "1_1") (pintype "passive"))
      (node (ref "U38") (pin "27") (pinfunction "ARXP4_27") (pintype "passive"))
    )
    (net (code "32") (name "/SATAPM0_RXP5") (class "Default")
      (node (ref "C363") (pin "2") (pinfunction "2_2") (pintype "passive"))
      (node (ref "U38") (pin "21") (pinfunction "ARXP5_21") (pintype "passive"))
    )
    (net (code "33") (name "/SATAPM0_RXP_0") (class "Default")
      (node (ref "C370") (pin "2") (pinfunction "2_2") (pintype "passive"))
      (node (ref "J6") (pin "6") (pinfunction "RXP_6") (pintype "passive"))
    )
    (net (code "34") (name "/SATAPM0_RXP_1") (class "Default")
      (node (ref "C354") (pin "2") (pinfunction "2_2") (pintype "passive"))
      (node (ref "J4") (pin "6") (pinfunction "RXP_6") (pintype "passive"))
    )
    (net (code "35") (name "/SATAPM0_RXP_2") (class "Default")
      (node (ref "C360") (pin "2") (pinfunction "2_2") (pintype "passive"))
      (node (ref "J5") (pin "6") (pinfunction "RXP_6") (pintype "passive"))
    )
    (net (code "36") (name "/SATAPM0_RXP_3") (class "Default")
      (node (ref "C374") (pin "2") (pinfunction "2_2") (pintype "passive"))
      (node (ref "J7") (pin "6") (pinfunction "RXP_6") (pintype "passive"))
    )
    (net (code "37") (name "/SATAPM0_RXP_4") (class "Default")
      (node (ref "C392") (pin "2") (pinfunction "2_2") (pintype "passive"))
      (node (ref "J8") (pin "6") (pinfunction "RXP_6") (pintype "passive"))
    )
    (net (code "38") (name "/SATAPM0_TESTn") (class "Default")
      (node (ref "R228") (pin "2") (pinfunction "2_2") (pintype "passive"))
      (node (ref "U38") (pin "20") (pinfunction "XTSTN_20") (pintype "passive"))
    )
    (net (code "39") (name "/SATAPM0_TXN0") (class "Default")
      (node (ref "C366") (pin "1") (pinfunction "1_1") (pintype "passive"))
      (node (ref "U38") (pin "47") (pinfunction "ATXN0_47") (pintype "passive"))
    )
    (net (code "40") (name "/SATAPM0_TXN1") (class "Default")
      (node (ref "C350") (pin "1") (pinfunction "1_1") (pintype "passive"))
      (node (ref "U38") (pin "59") (pinfunction "ATXN1_59") (pintype "passive"))
    )
    (net (code "41") (name "/SATAPM0_TXN2") (class "Default")
      (node (ref "C357") (pin "1") (pinfunction "1_1") (pintype "passive"))
      (node (ref "U38") (pin "53") (pinfunction "ATXN2_53") (pintype "passive"))
    )
    (net (code "42") (name "/SATAPM0_TXN3") (class "Default")
      (node (ref "C372") (pin "1") (pinfunction "1_1") (pintype "passive"))
      (node (ref "U38") (pin "36") (pinfunction "ATXN3_36") (pintype "passive"))
    )
    (net (code "43") (name "/SATAPM0_TXN4") (class "Default")
      (node (ref "C390") (pin "1") (pinfunction "1_1") (pintype "passive"))
      (node (ref "U38") (pin "30") (pinfunction "ATXN4_30") (pintype "passive"))
    )
    (net (code "44") (name "/SATAPM0_TXN5") (class "Default")
      (node (ref "C367") (pin "2") (pinfunction "2_2") (pintype "passive"))
      (node (ref "U38") (pin "24") (pinfunction "ATXN5_24") (pintype "passive"))
    )
    (net (code "45") (name "/SATAPM0_TXN_0") (class "Default")
      (node (ref "C366") (pin "2") (pinfunction "2_2") (pintype "passive"))
      (node (ref "J6") (pin "3") (pinfunction "TXN_3") (pintype "passive"))
    )
    (net (code "46") (name "/SATAPM0_TXN_1") (class "Default")
      (node (ref "C350") (pin "2") (pinfunction "2_2") (pintype "passive"))
      (node (ref "J4") (pin "3") (pinfunction "TXN_3") (pintype "passive"))
    )
    (net (code "47") (name "/SATAPM0_TXN_2") (class "Default")
      (node (ref "C357") (pin "2") (pinfunction "2_2") (pintype "passive"))
      (node (ref "J5") (pin "3") (pinfunction "TXN_3") (pintype "passive"))
    )
    (net (code "48") (name "/SATAPM0_TXN_3") (class "Default")
      (node (ref "C372") (pin "2") (pinfunction "2_2") (pintype "passive"))
      (node (ref "J7") (pin "3") (pinfunction "TXN_3") (pintype "passive"))
    )
    (net (code "49") (name "/SATAPM0_TXN_4") (class "Default")
      (node (ref "C390") (pin "2") (pinfunction "2_2") (pintype "passive"))
      (node (ref "J8") (pin "3") (pinfunction "TXN_3") (pintype "passive"))
    )
    (net (code "50") (name "/SATAPM0_TXP0") (class "Default")
      (node (ref "C364") (pin "1") (pinfunction "1_1") (pintype "passive"))
      (node (ref "U38") (pin "48") (pinfunction "ATXP0_48") (pintype "passive"))
    )
    (net (code "51") (name "/SATAPM0_TXP1") (class "Default")
      (node (ref "C349") (pin "1") (pinfunction "1_1") (pintype "passive"))
      (node (ref "U38") (pin "60") (pinfunction "ATXP1_60") (pintype "passive"))
    )
    (net (code "52") (name "/SATAPM0_TXP2") (class "Default")
      (node (ref "C356") (pin "1") (pinfunction "1_1") (pintype "passive"))
      (node (ref "U38") (pin "54") (pinfunction "ATXP2_54") (pintype "passive"))
    )
    (net (code "53") (name "/SATAPM0_TXP3") (class "Default")
      (node (ref "C371") (pin "1") (pinfunction "1_1") (pintype "passive"))
      (node (ref "U38") (pin "37") (pinfunction "ATXP3_37") (pintype "passive"))
    )
    (net (code "54") (name "/SATAPM0_TXP4") (class "Default")
      (node (ref "C389") (pin "1") (pinfunction "1_1") (pintype "passive"))
      (node (ref "U38") (pin "31") (pinfunction "ATXP4_31") (pintype "passive"))
    )
    (net (code "55") (name "/SATAPM0_TXP5") (class "Default")
      (node (ref "C369") (pin "2") (pinfunction "2_2") (pintype "passive"))
      (node (ref "U38") (pin "25") (pinfunction "ATXP5_25") (pintype "passive"))
    )
    (net (code "56") (name "/SATAPM0_TXP_0") (class "Default")
      (node (ref "C364") (pin "2") (pinfunction "2_2") (pintype "passive"))
      (node (ref "J6") (pin "2") (pinfunction "TXP_2") (pintype "passive"))
    )
    (net (code "57") (name "/SATAPM0_TXP_1") (class "Default")
      (node (ref "C349") (pin "2") (pinfunction "2_2") (pintype "passive"))
      (node (ref "J4") (pin "2") (pinfunction "TXP_2") (pintype "passive"))
    )
    (net (code "58") (name "/SATAPM0_TXP_2") (class "Default")
      (node (ref "C356") (pin "2") (pinfunction "2_2") (pintype "passive"))
      (node (ref "J5") (pin "2") (pinfunction "TXP_2") (pintype "passive"))
    )
    (net (code "59") (name "/SATAPM0_TXP_3") (class "Default")
      (node (ref "C371") (pin "2") (pinfunction "2_2") (pintype "passive"))
      (node (ref "J7") (pin "2") (pinfunction "TXP_2") (pintype "passive"))
    )
    (net (code "60") (name "/SATAPM0_TXP_4") (class "Default")
      (node (ref "C389") (pin "2") (pinfunction "2_2") (pintype "passive"))
      (node (ref "J8") (pin "2") (pinfunction "TXP_2") (pintype "passive"))
    )
    (net (code "61") (name "/SATAPM0_XIN") (class "Default")
      (node (ref "C362") (pin "1") (pinfunction "1_1") (pintype "passive"))
      (node (ref "R225") (pin "2") (pinfunction "2_2") (pintype "passive"))
      (node (ref "U38") (pin "39") (pinfunction "AXIN_39") (pintype "passive"))
      (node (ref "Y4") (pin "3") (pinfunction "X2_3") (pintype "passive"))
    )
    (net (code "62") (name "/SATAPM0_XOUT") (class "Default")
      (node (ref "C361") (pin "1") (pinfunction "1_1") (pintype "passive"))
      (node (ref "R225") (pin "1") (pinfunction "1_1") (pintype "passive"))
      (node (ref "U38") (pin "40") (pinfunction "AXOUT_40") (pintype "passive"))
      (node (ref "Y4") (pin "1") (pinfunction "X1_1") (pintype "passive"))
    )
    (net (code "63") (name "12V") (class "Default")
      (node (ref "R217") (pin "1") (pinfunction "1_1") (pintype "passive"))
    )
    (net (code "64") (name "GND") (class "Default")
      (node (ref "C347") (pin "2") (pinfunction "2_2") (pintype "passive"))
      (node (ref "C348") (pin "2") (pinfunction "2_2") (pintype "passive"))
      (node (ref "C351") (pin "2") (pinfunction "2_2") (pintype "passive"))
      (node (ref "C352") (pin "2") (pinfunction "2_2") (pintype "passive"))
      (node (ref "C355") (pin "2") (pinfunction "2_2") (pintype "passive"))
      (node (ref "C358") (pin "2") (pinfunction "2_2") (pintype "passive"))
      (node (ref "C361") (pin "2") (pinfunction "2_2") (pintype "passive"))
      (node (ref "C362") (pin "2") (pinfunction "2_2") (pintype "passive"))
      (node (ref "C375") (pin "2") (pinfunction "2_2") (pintype "passive"))
      (node (ref "C377") (pin "2") (pinfunction "2_2") (pintype "passive"))
      (node (ref "C378") (pin "2") (pinfunction "2_2") (pintype "passive"))
      (node (ref "C379") (pin "2") (pinfunction "2_2") (pintype "passive"))
      (node (ref "C380") (pin "2") (pinfunction "2_2") (pintype "passive"))
      (node (ref "C381") (pin "2") (pinfunction "2_2") (pintype "passive"))
      (node (ref "C382") (pin "2") (pinfunction "2_2") (pintype "passive"))
      (node (ref "C383") (pin "2") (pinfunction "2_2") (pintype "passive"))
      (node (ref "C384") (pin "2") (pinfunction "2_2") (pintype "passive"))
      (node (ref "C385") (pin "2") (pinfunction "2_2") (pintype "passive"))
      (node (ref "C386") (pin "2") (pinfunction "2_2") (pintype "passive"))
      (node (ref "C387") (pin "2") (pinfunction "2_2") (pintype "passive"))
      (node (ref "C388") (pin "2") (pinfunction "2_2") (pintype "passive"))
      (node (ref "C393") (pin "2") (pinfunction "2_2") (pintype "passive"))
      (node (ref "C395") (pin "2") (pinfunction "2_2") (pintype "passive"))
      (node (ref "C396") (pin "2") (pinfunction "2_2") (pintype "passive"))
      (node (ref "C397") (pin "2") (pinfunction "2_2") (pintype "passive"))
      (node (ref "C398") (pin "2") (pinfunction "2_2") (pintype "passive"))
      (node (ref "C399") (pin "2") (pinfunction "2_2") (pintype "passive"))
      (node (ref "C400") (pin "2") (pinfunction "2_2") (pintype "passive"))
      (node (ref "C401") (pin "2") (pinfunction "2_2") (pintype "passive"))
      (node (ref "C402") (pin "2") (pinfunction "2_2") (pintype "passive"))
      (node (ref "C403") (pin "2") (pinfunction "2_2") (pintype "passive"))
      (node (ref "C404") (pin "2") (pinfunction "2_2") (pintype "passive"))
      (node (ref "C405") (pin "2") (pinfunction "2_2") (pintype "passive"))
      (node (ref "C406") (pin "2") (pinfunction "2_2") (pintype "passive"))
      (node (ref "J3") (pin "2") (pinfunction "GND1_2") (pintype "passive"))
      (node (ref "J3") (pin "3") (pinfunction "GND2_3") (pintype "passive"))
      (node (ref "J4") (pin "1") (pinfunction "GND1_1") (pintype "passive"))
      (node (ref "J4") (pin "4") (pinfunction "GND2_4") (pintype "passive"))
      (node (ref "J4") (pin "7") (pinfunction "GND3_7") (pintype "passive"))
      (node (ref "J4") (pin "8") (pinfunction "GND4_8") (pintype "passive"))
      (node (ref "J4") (pin "9") (pinfunction "GND5_9") (pintype "passive"))
      (node (ref "J5") (pin "1") (pinfunction "GND1_1") (pintype "passive"))
      (node (ref "J5") (pin "4") (pinfunction "GND2_4") (pintype "passive"))
      (node (ref "J5") (pin "7") (pinfunction "GND3_7") (pintype "passive"))
      (node (ref "J5") (pin "8") (pinfunction "GND4_8") (pintype "passive"))
      (node (ref "J5") (pin "9") (pinfunction "GND5_9") (pintype "passive"))
      (node (ref "J6") (pin "1") (pinfunction "GND1_1") (pintype "passive"))
      (node (ref "J6") (pin "4") (pinfunction "GND2_4") (pintype "passive"))
      (node (ref "J6") (pin "7") (pinfunction "GND3_7") (pintype "passive"))
      (node (ref "J6") (pin "8") (pinfunction "GND4_8") (pintype "passive"))
      (node (ref "J6") (pin "9") (pinfunction "GND5_9") (pintype "passive"))
      (node (ref "J7") (pin "1") (pinfunction "GND1_1") (pintype "passive"))
      (node (ref "J7") (pin "4") (pinfunction "GND2_4") (pintype "passive"))
      (node (ref "J7") (pin "7") (pinfunction "GND3_7") (pintype "passive"))
      (node (ref "J7") (pin "8") (pinfunction "GND4_8") (pintype "passive"))
      (node (ref "J7") (pin "9") (pinfunction "GND5_9") (pintype "passive"))
      (node (ref "J8") (pin "1") (pinfunction "GND1_1") (pintype "passive"))
      (node (ref "J8") (pin "4") (pinfunction "GND2_4") (pintype "passive"))
      (node (ref "J8") (pin "7") (pinfunction "GND3_7") (pintype "passive"))
      (node (ref "J8") (pin "8") (pinfunction "GND4_8") (pintype "passive"))
      (node (ref "J8") (pin "9") (pinfunction "GND5_9") (pintype "passive"))
      (node (ref "R220") (pin "1") (pinfunction "1_1") (pintype "passive"))
      (node (ref "R224") (pin "2") (pinfunction "2_2") (pintype "passive"))
      (node (ref "R231") (pin "2") (pinfunction "2_2") (pintype "passive"))
      (node (ref "R234") (pin "2") (pinfunction "2_2") (pintype "passive"))
      (node (ref "U38") (pin "13") (pinfunction "DGND_2_13") (pintype "passive"))
      (node (ref "U38") (pin "41") (pinfunction "AGNDC_41") (pintype "passive"))
      (node (ref "U38") (pin "5") (pinfunction "DGND_1_5") (pintype "passive"))
      (node (ref "U38") (pin "65") (pinfunction "EPAD_65") (pintype "passive"))
      (node (ref "U39") (pin "4") (pinfunction "VSS_4") (pintype "passive"))
      (node (ref "U39") (pin "9") (pinfunction "EPAD_9") (pintype "passive"))
      (node (ref "U40") (pin "2") (pinfunction "GND_2") (pintype "passive"))
      (node (ref "U41") (pin "2") (pinfunction "GND_2") (pintype "passive"))
      (node (ref "Y4") (pin "2") (pinfunction "GND_2") (pintype "power_in"))
      (node (ref "Y4") (pin "4") (pinfunction "GND_4") (pintype "power_in"))
    )
    (net (code "65") (name "Net-(J3-+5V)") (class "Default")
      (node (ref "C347") (pin "1") (pinfunction "1_1") (pintype "passive"))
      (node (ref "C348") (pin "1") (pinfunction "1_1") (pintype "passive"))
      (node (ref "J3") (pin "1") (pinfunction "+5V_1") (pintype "passive"))
      (node (ref "R216") (pin "2") (pinfunction "2_2") (pintype "passive"))
    )
    (net (code "66") (name "Net-(J3-+12V)") (class "Default")
      (node (ref "C351") (pin "1") (pinfunction "1_1") (pintype "passive"))
      (node (ref "C352") (pin "1") (pinfunction "1_1") (pintype "passive"))
      (node (ref "J3") (pin "4") (pinfunction "+12V_4") (pintype "passive"))
      (node (ref "R217") (pin "2") (pinfunction "2_2") (pintype "passive"))
    )
    (net (code "67") (name "Net-(U40-EN)") (class "Default")
      (node (ref "C388") (pin "1") (pinfunction "1_1") (pintype "passive"))
      (node (ref "R230") (pin "2") (pinfunction "2_2") (pintype "passive"))
      (node (ref "U40") (pin "1") (pinfunction "EN_1") (pintype "passive"))
    )
    (net (code "68") (name "Net-(U40-FB{slash}OUT)") (class "Default")
      (node (ref "C376") (pin "2") (pinfunction "2_2") (pintype "passive"))
      (node (ref "R229") (pin "2") (pinfunction "2_2") (pintype "passive"))
      (node (ref "R231") (pin "1") (pinfunction "1_1") (pintype "passive"))
      (node (ref "U40") (pin "5") (pinfunction "FB/OUT_5") (pintype "passive"))
    )
    (net (code "69") (name "Net-(U40-LX)") (class "Default")
      (node (ref "L28") (pin "1") (pinfunction "1_1") (pintype "passive"))
      (node (ref "U40") (pin "3") (pinfunction "LX_3") (pintype "passive"))
    )
    (net (code "70") (name "Net-(U41-EN)") (class "Default")
      (node (ref "C406") (pin "1") (pinfunction "1_1") (pintype "passive"))
      (node (ref "R233") (pin "2") (pinfunction "2_2") (pintype "passive"))
      (node (ref "U41") (pin "1") (pinfunction "EN_1") (pintype "passive"))
    )
    (net (code "71") (name "Net-(U41-FB{slash}OUT)") (class "Default")
      (node (ref "C394") (pin "2") (pinfunction "2_2") (pintype "passive"))
      (node (ref "R232") (pin "2") (pinfunction "2_2") (pintype "passive"))
      (node (ref "R234") (pin "1") (pinfunction "1_1") (pintype "passive"))
      (node (ref "U41") (pin "5") (pinfunction "FB/OUT_5") (pintype "passive"))
    )
    (net (code "72") (name "Net-(U41-LX)") (class "Default")
      (node (ref "L29") (pin "1") (pinfunction "1_1") (pintype "passive"))
      (node (ref "U41") (pin "3") (pinfunction "LX_3") (pintype "passive"))
    )
    (net (code "73") (name "VCC3V3_SATAPM0") (class "Default")
      (node (ref "C358") (pin "1") (pinfunction "1_1") (pintype "passive"))
      (node (ref "C376") (pin "1") (pinfunction "1_1") (pintype "passive"))
      (node (ref "C377") (pin "1") (pinfunction "1_1") (pintype "passive"))
      (node (ref "C378") (pin "1") (pinfunction "1_1") (pintype "passive"))
      (node (ref "C379") (pin "1") (pinfunction "1_1") (pintype "passive"))
      (node (ref "C380") (pin "1") (pinfunction "1_1") (pintype "passive"))
      (node (ref "C381") (pin "1") (pinfunction "1_1") (pintype "passive"))
      (node (ref "C382") (pin "1") (pinfunction "1_1") (pintype "passive"))
      (node (ref "C383") (pin "1") (pinfunction "1_1") (pintype "passive"))
      (node (ref "C384") (pin "1") (pinfunction "1_1") (pintype "passive"))
      (node (ref "C385") (pin "1") (pinfunction "1_1") (pintype "passive"))
      (node (ref "C386") (pin "1") (pinfunction "1_1") (pintype "passive"))
      (node (ref "C387") (pin "1") (pinfunction "1_1") (pintype "passive"))
      (node (ref "L28") (pin "2") (pinfunction "2_2") (pintype "passive"))
      (node (ref "R218") (pin "1") (pinfunction "1_1") (pintype "passive"))
      (node (ref "R221") (pin "1") (pinfunction "1_1") (pintype "passive"))
      (node (ref "R222") (pin "1") (pinfunction "1_1") (pintype "passive"))
      (node (ref "R223") (pin "1") (pinfunction "1_1") (pintype "passive"))
      (node (ref "R226") (pin "1") (pinfunction "1_1") (pintype "passive"))
      (node (ref "R227") (pin "1") (pinfunction "1_1") (pintype "passive"))
      (node (ref "R228") (pin "1") (pinfunction "1_1") (pintype "passive"))
      (node (ref "R229") (pin "1") (pinfunction "1_1") (pintype "passive"))
      (node (ref "R233") (pin "1") (pinfunction "1_1") (pintype "passive"))
      (node (ref "U38") (pin "12") (pinfunction "DV33_2_12") (pintype "passive"))
      (node (ref "U38") (pin "26") (pinfunction "AV33_5_26") (pintype "passive"))
      (node (ref "U38") (pin "32") (pinfunction "AV33_4_32") (pintype "passive"))
      (node (ref "U38") (pin "38") (pinfunction "AV33_3_38") (pintype "passive"))
      (node (ref "U38") (pin "43") (pinfunction "AV33_C_43") (pintype "passive"))
      (node (ref "U38") (pin "49") (pinfunction "AV33_0_49") (pintype "passive"))
      (node (ref "U38") (pin "55") (pinfunction "AV33_2_55") (pintype "passive"))
      (node (ref "U38") (pin "6") (pinfunction "DV33_1_6") (pintype "passive"))
      (node (ref "U38") (pin "61") (pinfunction "AV33_1_61") (pintype "passive"))
      (node (ref "U39") (pin "8") (pinfunction "VCC_8") (pintype "passive"))
    )
    (net (code "74") (name "VDD1V2_SATAPM0") (class "Default")
      (node (ref "C394") (pin "1") (pinfunction "1_1") (pintype "passive"))
      (node (ref "C395") (pin "1") (pinfunction "1_1") (pintype "passive"))
      (node (ref "C396") (pin "1") (pinfunction "1_1") (pintype "passive"))
      (node (ref "C397") (pin "1") (pinfunction "1_1") (pintype "passive"))
      (node (ref "C398") (pin "1") (pinfunction "1_1") (pintype "passive"))
      (node (ref "C399") (pin "1") (pinfunction "1_1") (pintype "passive"))
      (node (ref "C400") (pin "1") (pinfunction "1_1") (pintype "passive"))
      (node (ref "C401") (pin "1") (pinfunction "1_1") (pintype "passive"))
      (node (ref "C402") (pin "1") (pinfunction "1_1") (pintype "passive"))
      (node (ref "C403") (pin "1") (pinfunction "1_1") (pintype "passive"))
      (node (ref "C404") (pin "1") (pinfunction "1_1") (pintype "passive"))
      (node (ref "C405") (pin "1") (pinfunction "1_1") (pintype "passive"))
      (node (ref "L29") (pin "2") (pinfunction "2_2") (pintype "passive"))
      (node (ref "R232") (pin "1") (pinfunction "1_1") (pintype "passive"))
      (node (ref "U38") (pin "14") (pinfunction "DV12_2_14") (pintype "passive"))
      (node (ref "U38") (pin "23") (pinfunction "AV12_5_23") (pintype "passive"))
      (node (ref "U38") (pin "29") (pinfunction "AV12_4_29") (pintype "passive"))
      (node (ref "U38") (pin "35") (pinfunction "AV12_3_35") (pintype "passive"))
      (node (ref "U38") (pin "4") (pinfunction "DV12_1_4") (pintype "passive"))
      (node (ref "U38") (pin "46") (pinfunction "AV12_0_46") (pintype "passive"))
      (node (ref "U38") (pin "52") (pinfunction "AV12_2_52") (pintype "passive"))
      (node (ref "U38") (pin "58") (pinfunction "AV12_1_58") (pintype "passive"))
    )
    (net (code "75") (name "VDDSATA_5V") (class "Default")
      (node (ref "C375") (pin "1") (pinfunction "1_1") (pintype "passive"))
      (node (ref "C393") (pin "1") (pinfunction "1_1") (pintype "passive"))
      (node (ref "R216") (pin "1") (pinfunction "1_1") (pintype "passive"))
      (node (ref "R230") (pin "1") (pinfunction "1_1") (pintype "passive"))
      (node (ref "U40") (pin "4") (pinfunction "VIN_4") (pintype "passive"))
      (node (ref "U41") (pin "4") (pinfunction "VIN_4") (pintype "passive"))
    )
    (net (code "76") (name "unconnected-(U38-ZGPIO05-Pad9)") (class "Default")
      (node (ref "U38") (pin "9") (pinfunction "ZGPIO05_9") (pintype "passive+no_connect"))
    )
    (net (code "77") (name "unconnected-(U38-ZGPIO06-Pad8)") (class "Default")
      (node (ref "U38") (pin "8") (pinfunction "ZGPIO06_8") (pintype "passive+no_connect"))
    )
    (net (code "78") (name "unconnected-(U38-ZGPIO07-Pad7)") (class "Default")
      (node (ref "U38") (pin "7") (pinfunction "ZGPIO07_7") (pintype "passive+no_connect"))
    )
    (net (code "79") (name "unconnected-(U38-ZGPIO08-Pad3)") (class "Default")
      (node (ref "U38") (pin "3") (pinfunction "ZGPIO08_3") (pintype "passive+no_connect"))
    )
    (net (code "80") (name "unconnected-(U38-ZGPIO09-Pad2)") (class "Default")
      (node (ref "U38") (pin "2") (pinfunction "ZGPIO09_2") (pintype "passive+no_connect"))
    )
    (net (code "81") (name "unconnected-(U38-ZGPIO10-Pad1)") (class "Default")
      (node (ref "U38") (pin "1") (pinfunction "ZGPIO10_1") (pintype "passive+no_connect"))
    )
    (net (code "82") (name "unconnected-(U38-ZGPIO11-Pad64)") (class "Default")
      (node (ref "U38") (pin "64") (pinfunction "ZGPIO11_64") (pintype "passive+no_connect"))
    )
  )
)
